# atmduinov2.net
KiCad netlist of a schematic drawn in EAGLE
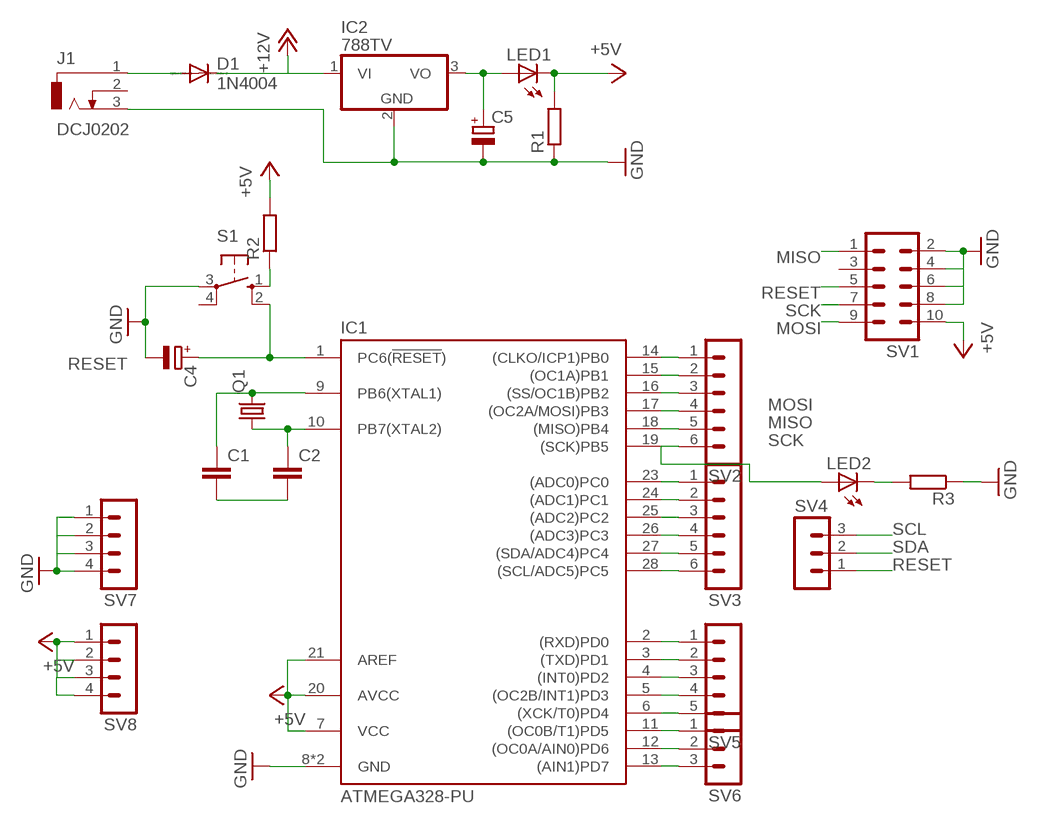
[diagram p0: schematic, sheet 1]

(export (version "E")
  (design (tool "Eeschema 10.0.6"))
  (components
    (comp (ref "C1")
      (value "C-EU025-024X044")
      (footprint "eagle-import:C025-024X044")
      (libsource (lib "eagle-import") (part "C-EU025-024X044"))
    )
    (comp (ref "C2")
      (value "C-EU025-024X044")
      (footprint "eagle-import:C025-024X044")
      (libsource (lib "eagle-import") (part "C-EU025-024X044"))
    )
    (comp (ref "C4")
      (value "CPOL-EUE1.8-4")
      (footprint "eagle-import:E1,8-4")
      (libsource (lib "eagle-import") (part "CPOL-EUE1.8-4"))
    )
    (comp (ref "C5")
      (value "CPOL-EUE1.8-4")
      (footprint "eagle-import:E1,8-4")
      (libsource (lib "eagle-import") (part "CPOL-EUE1.8-4"))
    )
    (comp (ref "D1")
      (value "1N4004")
      (footprint "eagle-import:DO41-10")
      (libsource (lib "eagle-import") (part "1N4004"))
    )
    (comp (ref "IC1")
      (value "ATMEGA328-PU")
      (footprint "eagle-import:DIL28")
      (fields (field (name "MF") "Microchip"))
      (libsource (lib "eagle-import") (part "ATMEGA328-PU"))
    )
    (comp (ref "IC2")
      (value "788TV")
      (footprint "eagle-import:TO220V")
      (libsource (lib "eagle-import") (part "78TV8"))
    )
    (comp (ref "J1")
      (value "DCJ0202")
      (footprint "eagle-import:DCJ0202")
      (libsource (lib "eagle-import") (part "DCJ0202"))
    )
    (comp (ref "LED1")
      (value "LED3MM")
      (footprint "eagle-import:LED3MM")
      (libsource (lib "eagle-import") (part "LED3MM"))
    )
    (comp (ref "LED2")
      (value "LED3MM")
      (footprint "eagle-import:LED3MM")
      (libsource (lib "eagle-import") (part "LED3MM"))
    )
    (comp (ref "Q1")
      (value "CRYSTALHC49S")
      (footprint "eagle-import:HC49_S")
      (libsource (lib "eagle-import") (part "CRYSTALHC49S"))
    )
    (comp (ref "R1")
      (value "R-EU_0204/5")
      (footprint "eagle-import:0204_5")
      (libsource (lib "eagle-import") (part "R-EU_0204/5"))
    )
    (comp (ref "R2")
      (value "R-EU_0204/5")
      (footprint "eagle-import:0204_5")
      (libsource (lib "eagle-import") (part "R-EU_0204/5"))
    )
    (comp (ref "R3")
      (value "R-EU_0204/5")
      (footprint "eagle-import:0204_5")
      (libsource (lib "eagle-import") (part "R-EU_0204/5"))
    )
    (comp (ref "S1")
      (value "10-XX")
      (footprint "eagle-import:B3F-10XX")
      (fields (field (name "MPN") "B3F-1000"))
      (libsource (lib "eagle-import") (part "10-XX"))
    )
    (comp (ref "SV1")
      (value "ML10")
      (footprint "eagle-import:ML10")
      (libsource (lib "eagle-import") (part "ML10"))
    )
    (comp (ref "SV2")
      (value "MA06-1")
      (footprint "eagle-import:MA06-1")
      (libsource (lib "eagle-import") (part "MA06-1"))
    )
    (comp (ref "SV3")
      (value "MA06-1")
      (footprint "eagle-import:MA06-1")
      (libsource (lib "eagle-import") (part "MA06-1"))
    )
    (comp (ref "SV4")
      (value "MA03-1")
      (footprint "eagle-import:MA03-1")
      (libsource (lib "eagle-import") (part "MA03-1"))
    )
    (comp (ref "SV5")
      (value "MA05-1")
      (footprint "eagle-import:MA05-1")
      (libsource (lib "eagle-import") (part "MA05-1"))
    )
    (comp (ref "SV6")
      (value "MA03-1")
      (footprint "eagle-import:MA03-1")
      (libsource (lib "eagle-import") (part "MA03-1"))
    )
    (comp (ref "SV7")
      (value "MA04-1")
      (footprint "eagle-import:MA04-1")
      (libsource (lib "eagle-import") (part "MA04-1"))
    )
    (comp (ref "SV8")
      (value "MA04-1")
      (footprint "eagle-import:MA04-1")
      (libsource (lib "eagle-import") (part "MA04-1"))
    )
  )
  (nets
    (net (code "1") (name "+5V") (class "Default")
      (node (ref "IC1") (pin "20") (pinfunction "AVCC_20") (pintype "power_in"))
      (node (ref "IC1") (pin "21") (pinfunction "AREF_21") (pintype "passive"))
      (node (ref "IC1") (pin "7") (pinfunction "VCC_7") (pintype "power_in"))
      (node (ref "LED1") (pin "K") (pinfunction "C_K") (pintype "passive"))
      (node (ref "R1") (pin "2") (pinfunction "2_2") (pintype "passive"))
      (node (ref "R2") (pin "2") (pinfunction "2_2") (pintype "passive"))
      (node (ref "SV1") (pin "10") (pinfunction "10_10") (pintype "passive"))
      (node (ref "SV8") (pin "1") (pinfunction "1_1") (pintype "passive"))
      (node (ref "SV8") (pin "2") (pinfunction "2_2") (pintype "passive"))
      (node (ref "SV8") (pin "3") (pinfunction "3_3") (pintype "passive"))
      (node (ref "SV8") (pin "4") (pinfunction "4_4") (pintype "passive"))
    )
    (net (code "2") (name "+12V") (class "Default")
      (node (ref "D1") (pin "C") (pinfunction "C_C") (pintype "passive"))
      (node (ref "IC2") (pin "1") (pinfunction "VI_1") (pintype "input"))
    )
    (net (code "3") (name "/MISO") (class "Default")
      (node (ref "IC1") (pin "18") (pinfunction "(MISO)PB4_18") (pintype "bidirectional"))
      (node (ref "SV1") (pin "1") (pinfunction "1_1") (pintype "passive"))
      (node (ref "SV2") (pin "5") (pinfunction "5_5") (pintype "passive"))
    )
    (net (code "4") (name "/MOSI") (class "Default")
      (node (ref "IC1") (pin "17") (pinfunction "(OC2A/MOSI)PB3_17") (pintype "bidirectional"))
      (node (ref "SV1") (pin "9") (pinfunction "9_9") (pintype "passive"))
      (node (ref "SV2") (pin "4") (pinfunction "4_4") (pintype "passive"))
    )
    (net (code "5") (name "/RESET") (class "Default")
      (node (ref "C4") (pin "+") (pinfunction "+_+") (pintype "passive"))
      (node (ref "IC1") (pin "1") (pinfunction "PC6(~{RESET})_1") (pintype "bidirectional"))
      (node (ref "S1") (pin "2") (pinfunction "S1_2") (pintype "passive"))
      (node (ref "SV1") (pin "5") (pinfunction "5_5") (pintype "passive"))
      (node (ref "SV4") (pin "1") (pinfunction "1_1") (pintype "passive"))
    )
    (net (code "6") (name "/SCK") (class "Default")
      (node (ref "IC1") (pin "19") (pinfunction "(SCK)PB5_19") (pintype "bidirectional"))
      (node (ref "LED2") (pin "A") (pinfunction "A_A") (pintype "passive"))
      (node (ref "SV1") (pin "7") (pinfunction "7_7") (pintype "passive"))
      (node (ref "SV2") (pin "6") (pinfunction "6_6") (pintype "passive"))
    )
    (net (code "7") (name "/SCL") (class "Default")
      (node (ref "IC1") (pin "28") (pinfunction "(SCL/ADC5)PC5_28") (pintype "bidirectional"))
      (node (ref "SV3") (pin "6") (pinfunction "6_6") (pintype "passive"))
      (node (ref "SV4") (pin "3") (pinfunction "3_3") (pintype "passive"))
    )
    (net (code "8") (name "/SDA") (class "Default")
      (node (ref "IC1") (pin "27") (pinfunction "(SDA/ADC4)PC4_27") (pintype "bidirectional"))
      (node (ref "SV3") (pin "5") (pinfunction "5_5") (pintype "passive"))
      (node (ref "SV4") (pin "2") (pinfunction "2_2") (pintype "passive"))
    )
    (net (code "9") (name "GND") (class "Default")
      (node (ref "C4") (pin "-") (pinfunction "-_-") (pintype "passive"))
      (node (ref "C5") (pin "-") (pinfunction "-_-") (pintype "passive"))
      (node (ref "IC1") (pin "22") (pinfunction "GND_22") (pintype "power_in"))
      (node (ref "IC1") (pin "8") (pinfunction "GND_8") (pintype "power_in"))
      (node (ref "IC2") (pin "2") (pinfunction "GND_2") (pintype "passive"))
      (node (ref "J1") (pin "3") (pinfunction "3_3") (pintype "passive"))
      (node (ref "R1") (pin "1") (pinfunction "1_1") (pintype "passive"))
      (node (ref "R3") (pin "1") (pinfunction "1_1") (pintype "passive"))
      (node (ref "S1") (pin "3") (pinfunction "P_3") (pintype "passive"))
      (node (ref "SV1") (pin "2") (pinfunction "2_2") (pintype "passive"))
      (node (ref "SV1") (pin "4") (pinfunction "4_4") (pintype "passive"))
      (node (ref "SV1") (pin "6") (pinfunction "6_6") (pintype "passive"))
      (node (ref "SV1") (pin "8") (pinfunction "8_8") (pintype "passive"))
      (node (ref "SV7") (pin "1") (pinfunction "1_1") (pintype "passive"))
      (node (ref "SV7") (pin "2") (pinfunction "2_2") (pintype "passive"))
      (node (ref "SV7") (pin "3") (pinfunction "3_3") (pintype "passive"))
      (node (ref "SV7") (pin "4") (pinfunction "4_4") (pintype "passive"))
    )
    (net (code "10") (name "Net-(C1-Pad2)") (class "Default")
      (node (ref "C1") (pin "2") (pinfunction "2_2") (pintype "passive"))
      (node (ref "C2") (pin "2") (pinfunction "2_2") (pintype "passive"))
    )
    (net (code "11") (name "Net-(D1-PadA)") (class "Default")
      (node (ref "D1") (pin "A") (pinfunction "A_A") (pintype "passive"))
      (node (ref "J1") (pin "1") (pinfunction "1_1") (pintype "passive"))
    )
    (net (code "12") (name "Net-(IC1-(ADC0)PC0)") (class "Default")
      (node (ref "IC1") (pin "23") (pinfunction "(ADC0)PC0_23") (pintype "bidirectional"))
      (node (ref "SV3") (pin "1") (pinfunction "1_1") (pintype "passive"))
    )
    (net (code "13") (name "Net-(IC1-(ADC1)PC1)") (class "Default")
      (node (ref "IC1") (pin "24") (pinfunction "(ADC1)PC1_24") (pintype "bidirectional"))
      (node (ref "SV3") (pin "2") (pinfunction "2_2") (pintype "passive"))
    )
    (net (code "14") (name "Net-(IC1-(ADC2)PC2)") (class "Default")
      (node (ref "IC1") (pin "25") (pinfunction "(ADC2)PC2_25") (pintype "bidirectional"))
      (node (ref "SV3") (pin "3") (pinfunction "3_3") (pintype "passive"))
    )
    (net (code "15") (name "Net-(IC1-(ADC3)PC3)") (class "Default")
      (node (ref "IC1") (pin "26") (pinfunction "(ADC3)PC3_26") (pintype "bidirectional"))
      (node (ref "SV3") (pin "4") (pinfunction "4_4") (pintype "passive"))
    )
    (net (code "16") (name "Net-(IC1-(AIN1)PD7)") (class "Default")
      (node (ref "IC1") (pin "13") (pinfunction "(AIN1)PD7_13") (pintype "bidirectional"))
      (node (ref "SV6") (pin "3") (pinfunction "3_3") (pintype "passive"))
    )
    (net (code "17") (name "Net-(IC1-(CLKO{slash}ICP1)PB0)") (class "Default")
      (node (ref "IC1") (pin "14") (pinfunction "(CLKO/ICP1)PB0_14") (pintype "bidirectional"))
      (node (ref "SV2") (pin "1") (pinfunction "1_1") (pintype "passive"))
    )
    (net (code "18") (name "Net-(IC1-(INT0)PD2)") (class "Default")
      (node (ref "IC1") (pin "4") (pinfunction "(INT0)PD2_4") (pintype "bidirectional"))
      (node (ref "SV5") (pin "3") (pinfunction "3_3") (pintype "passive"))
    )
    (net (code "19") (name "Net-(IC1-(OC0A{slash}AIN0)PD6)") (class "Default")
      (node (ref "IC1") (pin "12") (pinfunction "(OC0A/AIN0)PD6_12") (pintype "bidirectional"))
      (node (ref "SV6") (pin "2") (pinfunction "2_2") (pintype "passive"))
    )
    (net (code "20") (name "Net-(IC1-(OC0B{slash}T1)PD5)") (class "Default")
      (node (ref "IC1") (pin "11") (pinfunction "(OC0B/T1)PD5_11") (pintype "bidirectional"))
      (node (ref "SV6") (pin "1") (pinfunction "1_1") (pintype "passive"))
    )
    (net (code "21") (name "Net-(IC1-(OC1A)PB1)") (class "Default")
      (node (ref "IC1") (pin "15") (pinfunction "(OC1A)PB1_15") (pintype "bidirectional"))
      (node (ref "SV2") (pin "2") (pinfunction "2_2") (pintype "passive"))
    )
    (net (code "22") (name "Net-(IC1-(OC2B{slash}INT1)PD3)") (class "Default")
      (node (ref "IC1") (pin "5") (pinfunction "(OC2B/INT1)PD3_5") (pintype "bidirectional"))
      (node (ref "SV5") (pin "4") (pinfunction "4_4") (pintype "passive"))
    )
    (net (code "23") (name "Net-(IC1-(RXD)PD0)") (class "Default")
      (node (ref "IC1") (pin "2") (pinfunction "(RXD)PD0_2") (pintype "bidirectional"))
      (node (ref "SV5") (pin "1") (pinfunction "1_1") (pintype "passive"))
    )
    (net (code "24") (name "Net-(IC1-(SS{slash}OC1B)PB2)") (class "Default")
      (node (ref "IC1") (pin "16") (pinfunction "(SS/OC1B)PB2_16") (pintype "bidirectional"))
      (node (ref "SV2") (pin "3") (pinfunction "3_3") (pintype "passive"))
    )
    (net (code "25") (name "Net-(IC1-(TXD)PD1)") (class "Default")
      (node (ref "IC1") (pin "3") (pinfunction "(TXD)PD1_3") (pintype "bidirectional"))
      (node (ref "SV5") (pin "2") (pinfunction "2_2") (pintype "passive"))
    )
    (net (code "26") (name "Net-(IC1-(XCK{slash}T0)PD4)") (class "Default")
      (node (ref "IC1") (pin "6") (pinfunction "(XCK/T0)PD4_6") (pintype "bidirectional"))
      (node (ref "SV5") (pin "5") (pinfunction "5_5") (pintype "passive"))
    )
    (net (code "27") (name "Net-(IC1-PB6(XTAL1))") (class "Default")
      (node (ref "C1") (pin "1") (pinfunction "1_1") (pintype "passive"))
      (node (ref "IC1") (pin "9") (pinfunction "PB6(XTAL1)_9") (pintype "bidirectional"))
      (node (ref "Q1") (pin "2") (pinfunction "2_2") (pintype "passive"))
    )
    (net (code "28") (name "Net-(IC1-PB7(XTAL2))") (class "Default")
      (node (ref "C2") (pin "1") (pinfunction "1_1") (pintype "passive"))
      (node (ref "IC1") (pin "10") (pinfunction "PB7(XTAL2)_10") (pintype "bidirectional"))
      (node (ref "Q1") (pin "1") (pinfunction "1_1") (pintype "passive"))
    )
    (net (code "29") (name "Net-(IC2-VO)") (class "Default")
      (node (ref "C5") (pin "+") (pinfunction "+_+") (pintype "passive"))
      (node (ref "IC2") (pin "3") (pinfunction "VO_3") (pintype "passive"))
      (node (ref "LED1") (pin "A") (pinfunction "A_A") (pintype "passive"))
    )
    (net (code "30") (name "Net-(LED2-C)") (class "Default")
      (node (ref "LED2") (pin "K") (pinfunction "C_K") (pintype "passive"))
      (node (ref "R3") (pin "2") (pinfunction "2_2") (pintype "passive"))
    )
    (net (code "31") (name "Net-(S1-S)") (class "Default")
      (node (ref "R2") (pin "1") (pinfunction "1_1") (pintype "passive"))
      (node (ref "S1") (pin "1") (pinfunction "S_1") (pintype "passive"))
    )
    (net (code "32") (name "unconnected-(J1-Pad2)") (class "Default")
      (node (ref "J1") (pin "2") (pinfunction "2_2") (pintype "passive"))
    )
    (net (code "33") (name "unconnected-(S1-P1-Pad4)") (class "Default")
      (node (ref "S1") (pin "4") (pinfunction "P1_4") (pintype "passive"))
    )
    (net (code "34") (name "unconnected-(SV1-Pad3)") (class "Default")
      (node (ref "SV1") (pin "3") (pinfunction "3_3") (pintype "passive"))
    )
  )
)
